# Main_Schematic.net
KiCad netlist of a schematic drawn in Altium Designer
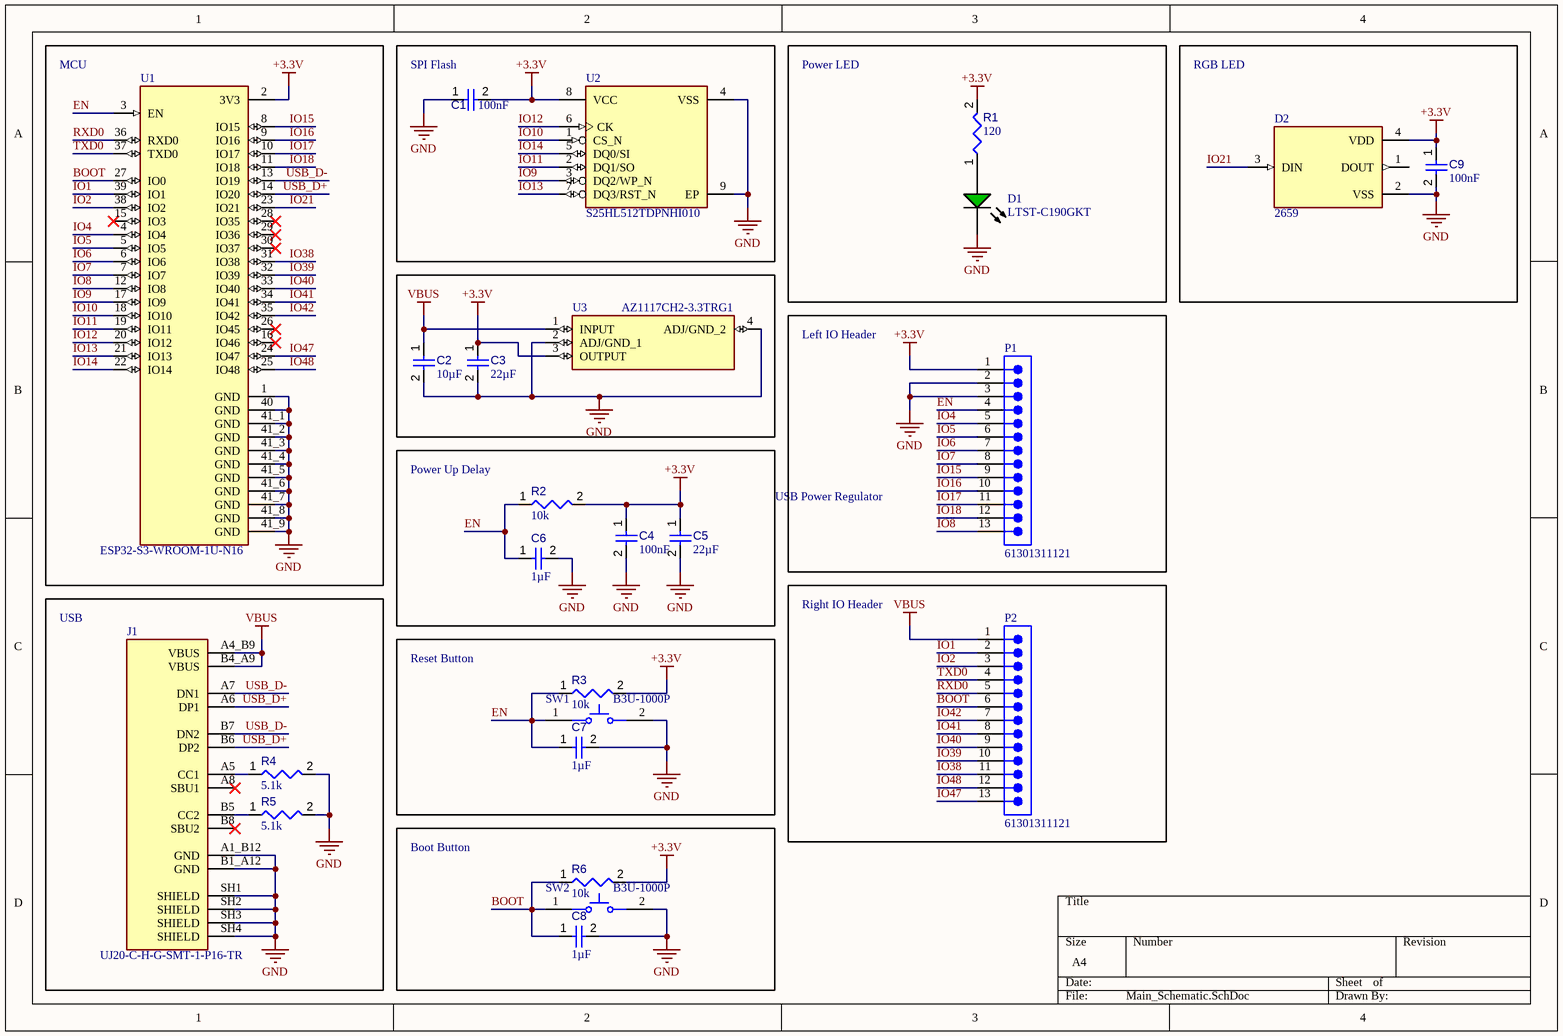
[diagram p0: Main_Schematic.SchDoc]

(export (version "E")
  (design (tool "Eeschema 10.0.6"))
  (components
    (comp (ref "C1")
      (value "100nF")
      (footprint "CAPC1608X90X40NL10T20")
      (description "Chip Capacitor, 100 nF, +/- 10%, 50 V, 0603 (1608 Metric)")
      (fields (field (name "TOLERANCE") "10%") (field (name "Comment") "Capacitor 100 nF +/-10% 50 V 0603"))
      (libsource (lib "Rory Cook") (part "CAP-NP-2"))
    )
    (comp (ref "C2")
      (value "10µF")
      (footprint "CAPC0603(1608)100_L")
      (description "Chip Capacitor, 10µF +/-20%, 10V, 0603, Thickness 1 mm")
      (fields (field (name "TOLERANCE") "10%") (field (name "Comment") "Capacitor 10µF +/-20% 10V 0603"))
      (libsource (lib "Rory Cook") (part "CAP-NP-2"))
    )
    (comp (ref "C3")
      (value "22µF")
      (footprint "CAPC0603(1608)100_L")
      (description "Chip Capacitor, 10µF +/-20%, 10V, 0603, Thickness 1 mm")
      (fields (field (name "TOLERANCE") "10%") (field (name "Comment") "Capacitor 10µF +/-20% 10V 0603"))
      (libsource (lib "Rory Cook") (part "CAP-NP-2"))
    )
    (comp (ref "C4")
      (value "100nF")
      (footprint "CAPC1608X90X40NL10T20")
      (description "Chip Capacitor, 100 nF, +/- 10%, 50 V, 0603 (1608 Metric)")
      (fields (field (name "TOLERANCE") "10%") (field (name "Comment") "Capacitor 100 nF +/-10% 50 V 0603"))
      (libsource (lib "Rory Cook") (part "CAP-NP-2"))
    )
    (comp (ref "C5")
      (value "22µF")
      (footprint "CAPC0603(1608)100_L")
      (description "Chip Capacitor, 10µF +/-20%, 10V, 0603, Thickness 1 mm")
      (fields (field (name "TOLERANCE") "10%") (field (name "Comment") "Capacitor 10µF +/-20% 10V 0603"))
      (libsource (lib "Rory Cook") (part "CAP-NP-2"))
    )
    (comp (ref "C6")
      (value "1µF")
      (footprint "CAPC1608X94X35NL15T15")
      (description "Chip Capacitor, 1 uF, +/- 10%, 16 V, 0603 (1608 Metric)")
      (fields (field (name "TOLERANCE") "10%") (field (name "Comment") "Capacitor 1 uF +/- 10% 16 V 0603"))
      (libsource (lib "Rory Cook") (part "CAP-NP-2"))
    )
    (comp (ref "C7")
      (value "1µF")
      (footprint "CAPC1608X94X35NL15T15")
      (description "Chip Capacitor, 1 uF, +/- 10%, 16 V, 0603 (1608 Metric)")
      (fields (field (name "TOLERANCE") "10%") (field (name "Comment") "Capacitor 1 uF +/- 10% 16 V 0603"))
      (libsource (lib "Rory Cook") (part "CAP-NP-2"))
    )
    (comp (ref "C8")
      (value "1µF")
      (footprint "CAPC1608X94X35NL15T15")
      (description "Chip Capacitor, 1 uF, +/- 10%, 16 V, 0603 (1608 Metric)")
      (fields (field (name "TOLERANCE") "10%") (field (name "Comment") "Capacitor 1 uF +/- 10% 16 V 0603"))
      (libsource (lib "Rory Cook") (part "CAP-NP-2"))
    )
    (comp (ref "C9")
      (value "100nF")
      (footprint "CAPC1608X90X40NL10T20")
      (description "Chip Capacitor, 100 nF, +/- 10%, 50 V, 0603 (1608 Metric)")
      (fields (field (name "TOLERANCE") "10%") (field (name "Comment") "Capacitor 100 nF +/-10% 50 V 0603"))
      (libsource (lib "Rory Cook") (part "CAP-NP-2"))
    )
    (comp (ref "D1")
      (value "LTST-C190GKT")
      (footprint "LTST-C190GKT_V")
      (description "LED Uni-Color Green, 100 mW, 30 mA, -55 to 85 degC, 2-Pin SMD, RoHS, Tape and Reel")
      (fields (field (name "POWER") "100mW") (field (name "MANUFACTURER") "Lite-On"))
      (libsource (lib "Rory Cook") (part "LED-GREEN-AK-2"))
    )
    (comp (ref "D2")
      (value "2659")
      (footprint "2659")
      (description "20 AWG Hook-Up Wire 26/34 White 300V 40.00' _12.19m_")
      (fields (field (name "MF") "Adafruit Industries") (field (name "DIGI-KEY_PART_NUMBER") "2183-2659-ND"))
      (libsource (lib "2659") (part "2659"))
    )
    (comp (ref "J1")
      (value "UJ20-C-H-G-SMT-1-P16-TR")
      (footprint "SAMESKY_UJ20-C-H-G-SMT-1-P16-TR")
      (fields (field (name "MF") "Same Sky"))
      (libsource (lib "Rory Cook") (part "UJ20-C-H-G-SMT-1-P16-TR"))
    )
    (comp (ref "P1")
      (value "61301311121")
      (footprint "61301311121")
      (description "Header, 2.54 Mm, Pin Header, 13 Pins, Single Row, 3A, Wr-phd Series")
      (libsource (lib "Rory Cook") (part "Header_Male_1R_13P"))
    )
    (comp (ref "P2")
      (value "61301311121")
      (footprint "61301311121")
      (description "Header, 2.54 Mm, Pin Header, 13 Pins, Single Row, 3A, Wr-phd Series")
      (libsource (lib "Rory Cook") (part "Header_Male_1R_13P"))
    )
    (comp (ref "R1")
      (value "120")
      (footprint "RESC0603(1608)_L")
      (description "Chip Resistor, 120 Ohms, +/-5 %, 0.1 W, -55 to 155 degC, 0603")
      (fields (field (name "POWER") "100mW") (field (name "TOLERANCE") "5%"))
      (libsource (lib "Rory Cook") (part "RES-2"))
    )
    (comp (ref "R2")
      (value "10k")
      (footprint "RESC1608X55X25ML10T15")
      (description "Chip Resistor, 10 KOhm, +/- 1%, 01 W, -55 to 155 degC, 0603 (1608 Metric)")
      (fields (field (name "POWER") "100mW") (field (name "TOLERANCE") "1%"))
      (libsource (lib "Rory Cook") (part "RES-2"))
    )
    (comp (ref "R3")
      (value "10k")
      (footprint "RESC1608X55X25ML10T15")
      (description "Chip Resistor, 10 KOhm, +/- 1%, 01 W, -55 to 155 degC, 0603 (1608 Metric)")
      (fields (field (name "POWER") "100mW") (field (name "TOLERANCE") "1%"))
      (libsource (lib "Rory Cook") (part "RES-2"))
    )
    (comp (ref "R4")
      (value "5.1k")
      (footprint "RESC1608X55X25ML10T15")
      (description "Chip Resistor, 4.7 KOhm, +/- 1%, 0.1 W, -55 to 155 degC, 0603 (1608 Metric)")
      (fields (field (name "TOLERANCE") "1%") (field (name "POWER") "100mW"))
      (libsource (lib "Rory Cook") (part "RES-2"))
    )
    (comp (ref "R5")
      (value "5.1k")
      (footprint "RESC1608X55X25ML10T15")
      (description "Chip Resistor, 4.7 KOhm, +/- 1%, 0.1 W, -55 to 155 degC, 0603 (1608 Metric)")
      (fields (field (name "TOLERANCE") "1%") (field (name "POWER") "100mW"))
      (libsource (lib "Rory Cook") (part "RES-2"))
    )
    (comp (ref "R6")
      (value "10k")
      (footprint "RESC1608X55X25ML10T15")
      (description "Chip Resistor, 10 KOhm, +/- 1%, 01 W, -55 to 155 degC, 0603 (1608 Metric)")
      (fields (field (name "POWER") "100mW") (field (name "TOLERANCE") "1%"))
      (libsource (lib "Rory Cook") (part "RES-2"))
    )
    (comp (ref "SW1")
      (value "B3U-1000P")
      (footprint "OMRON-B3U-1000_V")
      (description "Tactile Switch, SPST-NO, 0.05 A, 12 V, -25 to 70 degC, 2-Pin SMD, RoHS, Tape and Reel")
      (fields (field (name "MANUFACTURER") "Omron Electronic Components"))
      (libsource (lib "Rory Cook") (part "SW-SPST-NO-2"))
    )
    (comp (ref "SW2")
      (value "B3U-1000P")
      (footprint "OMRON-B3U-1000_V")
      (description "Tactile Switch, SPST-NO, 0.05 A, 12 V, -25 to 70 degC, 2-Pin SMD, RoHS, Tape and Reel")
      (fields (field (name "MANUFACTURER") "Omron Electronic Components"))
      (libsource (lib "Rory Cook") (part "SW-SPST-NO-2"))
    )
    (comp (ref "U1")
      (value "ESP32-S3-WROOM-1U-N16")
      (footprint "XCVR_ESP32-S3-WROOM-1U-N16")
      (fields (field (name "MF") "Espressif Systems"))
      (libsource (lib "Rory Cook") (part "ESP32-S3-WROOM-1U-N16"))
    )
    (comp (ref "U2")
      (value "S25HL512TDPNHI010")
      (footprint "SON127P800X600X80-9N-V1")
      (description "512 Mb, SEMPER Flash Quad SPI")
      (fields (field (name "MANUFACTURER") "Infineon Technologies"))
      (libsource (lib "Rory Cook") (part "S25HL512TDPNHI010"))
    )
    (comp (ref "U3")
      (value "AZ1117CH2-3.3TRG1")
      (footprint "SOT230P700X180-4N")
      (description "Linear Voltage Regulator IC Positive Fixed 1 Output 1A SOT-223-3")
      (fields (field (name "MF") "Diodes Inc."))
      (libsource (lib "AZ1117CH2-3.3TRG1") (part "AZ1117CH2-3.3TRG1"))
    )
  )
  (nets
    (net (code "1") (name "+3.3V") (class "Default")
      (node (ref "C1") (pin "2") (pinfunction "2_2") (pintype "passive"))
      (node (ref "C3") (pin "1") (pinfunction "1_1") (pintype "passive"))
      (node (ref "C4") (pin "1") (pinfunction "1_1") (pintype "passive"))
      (node (ref "C5") (pin "1") (pinfunction "1_1") (pintype "passive"))
      (node (ref "C9") (pin "1") (pinfunction "1_1") (pintype "passive"))
      (node (ref "D2") (pin "4") (pinfunction "VDD_4") (pintype "power_in"))
      (node (ref "P1") (pin "1") (pinfunction "1_1") (pintype "passive"))
      (node (ref "R1") (pin "2") (pinfunction "2_2") (pintype "passive"))
      (node (ref "R2") (pin "2") (pinfunction "2_2") (pintype "passive"))
      (node (ref "R3") (pin "2") (pinfunction "2_2") (pintype "passive"))
      (node (ref "R6") (pin "2") (pinfunction "2_2") (pintype "passive"))
      (node (ref "U1") (pin "2") (pinfunction "3V3_2") (pintype "power_in"))
      (node (ref "U2") (pin "8") (pinfunction "VCC_8") (pintype "power_in"))
      (node (ref "U3") (pin "3") (pinfunction "OUTPUT_3") (pintype "bidirectional"))
    )
    (net (code "2") (name "/BOOT") (class "Default")
      (node (ref "C8") (pin "1") (pinfunction "1_1") (pintype "passive"))
      (node (ref "P2") (pin "6") (pinfunction "6_6") (pintype "passive"))
      (node (ref "R6") (pin "1") (pinfunction "1_1") (pintype "passive"))
      (node (ref "SW2") (pin "1") (pinfunction "1_1") (pintype "passive"))
      (node (ref "U1") (pin "27") (pinfunction "IO0_27") (pintype "bidirectional"))
    )
    (net (code "3") (name "/EN") (class "Default")
      (node (ref "C6") (pin "1") (pinfunction "1_1") (pintype "passive"))
      (node (ref "C7") (pin "1") (pinfunction "1_1") (pintype "passive"))
      (node (ref "P1") (pin "4") (pinfunction "4_4") (pintype "passive"))
      (node (ref "R2") (pin "1") (pinfunction "1_1") (pintype "passive"))
      (node (ref "R3") (pin "1") (pinfunction "1_1") (pintype "passive"))
      (node (ref "SW1") (pin "1") (pinfunction "1_1") (pintype "passive"))
      (node (ref "U1") (pin "3") (pinfunction "EN_3") (pintype "input"))
    )
    (net (code "4") (name "/IO1") (class "Default")
      (node (ref "P2") (pin "2") (pinfunction "2_2") (pintype "passive"))
      (node (ref "U1") (pin "39") (pinfunction "IO1_39") (pintype "bidirectional"))
    )
    (net (code "5") (name "/IO2") (class "Default")
      (node (ref "P2") (pin "3") (pinfunction "3_3") (pintype "passive"))
      (node (ref "U1") (pin "38") (pinfunction "IO2_38") (pintype "bidirectional"))
    )
    (net (code "6") (name "/IO4") (class "Default")
      (node (ref "P1") (pin "5") (pinfunction "5_5") (pintype "passive"))
      (node (ref "U1") (pin "4") (pinfunction "IO4_4") (pintype "bidirectional"))
    )
    (net (code "7") (name "/IO5") (class "Default")
      (node (ref "P1") (pin "6") (pinfunction "6_6") (pintype "passive"))
      (node (ref "U1") (pin "5") (pinfunction "IO5_5") (pintype "bidirectional"))
    )
    (net (code "8") (name "/IO6") (class "Default")
      (node (ref "P1") (pin "7") (pinfunction "7_7") (pintype "passive"))
      (node (ref "U1") (pin "6") (pinfunction "IO6_6") (pintype "bidirectional"))
    )
    (net (code "9") (name "/IO7") (class "Default")
      (node (ref "P1") (pin "8") (pinfunction "8_8") (pintype "passive"))
      (node (ref "U1") (pin "7") (pinfunction "IO7_7") (pintype "bidirectional"))
    )
    (net (code "10") (name "/IO8") (class "Default")
      (node (ref "P1") (pin "13") (pinfunction "13_13") (pintype "passive"))
      (node (ref "U1") (pin "12") (pinfunction "IO8_12") (pintype "bidirectional"))
    )
    (net (code "11") (name "/IO9") (class "Default")
      (node (ref "U1") (pin "17") (pinfunction "IO9_17") (pintype "bidirectional"))
      (node (ref "U2") (pin "3") (pinfunction "DQ2/WP_N_3") (pintype "bidirectional"))
    )
    (net (code "12") (name "/IO10") (class "Default")
      (node (ref "U1") (pin "18") (pinfunction "IO10_18") (pintype "bidirectional"))
      (node (ref "U2") (pin "1") (pinfunction "CS_N_1") (pintype "input"))
    )
    (net (code "13") (name "/IO11") (class "Default")
      (node (ref "U1") (pin "19") (pinfunction "IO11_19") (pintype "bidirectional"))
      (node (ref "U2") (pin "2") (pinfunction "DQ1/SO_2") (pintype "bidirectional"))
    )
    (net (code "14") (name "/IO12") (class "Default")
      (node (ref "U1") (pin "20") (pinfunction "IO12_20") (pintype "bidirectional"))
      (node (ref "U2") (pin "6") (pinfunction "CK_6") (pintype "input"))
    )
    (net (code "15") (name "/IO13") (class "Default")
      (node (ref "U1") (pin "21") (pinfunction "IO13_21") (pintype "bidirectional"))
      (node (ref "U2") (pin "7") (pinfunction "DQ3/RST_N_7") (pintype "bidirectional"))
    )
    (net (code "16") (name "/IO14") (class "Default")
      (node (ref "U1") (pin "22") (pinfunction "IO14_22") (pintype "bidirectional"))
      (node (ref "U2") (pin "5") (pinfunction "DQ0/SI_5") (pintype "bidirectional"))
    )
    (net (code "17") (name "/IO15") (class "Default")
      (node (ref "P1") (pin "9") (pinfunction "9_9") (pintype "passive"))
      (node (ref "U1") (pin "8") (pinfunction "IO15_8") (pintype "bidirectional"))
    )
    (net (code "18") (name "/IO16") (class "Default")
      (node (ref "P1") (pin "10") (pinfunction "10_10") (pintype "passive"))
      (node (ref "U1") (pin "9") (pinfunction "IO16_9") (pintype "bidirectional"))
    )
    (net (code "19") (name "/IO17") (class "Default")
      (node (ref "P1") (pin "11") (pinfunction "11_11") (pintype "passive"))
      (node (ref "U1") (pin "10") (pinfunction "IO17_10") (pintype "bidirectional"))
    )
    (net (code "20") (name "/IO18") (class "Default")
      (node (ref "P1") (pin "12") (pinfunction "12_12") (pintype "passive"))
      (node (ref "U1") (pin "11") (pinfunction "IO18_11") (pintype "bidirectional"))
    )
    (net (code "21") (name "/IO21") (class "Default")
      (node (ref "D2") (pin "3") (pinfunction "DIN_3") (pintype "input"))
      (node (ref "U1") (pin "23") (pinfunction "IO21_23") (pintype "bidirectional"))
    )
    (net (code "22") (name "/IO38") (class "Default")
      (node (ref "P2") (pin "11") (pinfunction "11_11") (pintype "passive"))
      (node (ref "U1") (pin "31") (pinfunction "IO38_31") (pintype "bidirectional"))
    )
    (net (code "23") (name "/IO39") (class "Default")
      (node (ref "P2") (pin "10") (pinfunction "10_10") (pintype "passive"))
      (node (ref "U1") (pin "32") (pinfunction "IO39_32") (pintype "bidirectional"))
    )
    (net (code "24") (name "/IO40") (class "Default")
      (node (ref "P2") (pin "9") (pinfunction "9_9") (pintype "passive"))
      (node (ref "U1") (pin "33") (pinfunction "IO40_33") (pintype "bidirectional"))
    )
    (net (code "25") (name "/IO41") (class "Default")
      (node (ref "P2") (pin "8") (pinfunction "8_8") (pintype "passive"))
      (node (ref "U1") (pin "34") (pinfunction "IO41_34") (pintype "bidirectional"))
    )
    (net (code "26") (name "/IO42") (class "Default")
      (node (ref "P2") (pin "7") (pinfunction "7_7") (pintype "passive"))
      (node (ref "U1") (pin "35") (pinfunction "IO42_35") (pintype "bidirectional"))
    )
    (net (code "27") (name "/IO47") (class "Default")
      (node (ref "P2") (pin "13") (pinfunction "13_13") (pintype "passive"))
      (node (ref "U1") (pin "24") (pinfunction "IO47_24") (pintype "bidirectional"))
    )
    (net (code "28") (name "/IO48") (class "Default")
      (node (ref "P2") (pin "12") (pinfunction "12_12") (pintype "passive"))
      (node (ref "U1") (pin "25") (pinfunction "IO48_25") (pintype "bidirectional"))
    )
    (net (code "29") (name "/RXD0") (class "Default")
      (node (ref "P2") (pin "5") (pinfunction "5_5") (pintype "passive"))
      (node (ref "U1") (pin "36") (pinfunction "RXD0_36") (pintype "bidirectional"))
    )
    (net (code "30") (name "/TXD0") (class "Default")
      (node (ref "P2") (pin "4") (pinfunction "4_4") (pintype "passive"))
      (node (ref "U1") (pin "37") (pinfunction "TXD0_37") (pintype "bidirectional"))
    )
    (net (code "31") (name "/USB_D+") (class "Default")
      (node (ref "J1") (pin "A6") (pinfunction "DP1_A6") (pintype "passive"))
      (node (ref "J1") (pin "B6") (pinfunction "DP2_B6") (pintype "passive"))
      (node (ref "U1") (pin "14") (pinfunction "IO20_14") (pintype "bidirectional"))
    )
    (net (code "32") (name "/USB_D-") (class "Default")
      (node (ref "J1") (pin "A7") (pinfunction "DN1_A7") (pintype "passive"))
      (node (ref "J1") (pin "B7") (pinfunction "DN2_B7") (pintype "passive"))
      (node (ref "U1") (pin "13") (pinfunction "IO19_13") (pintype "bidirectional"))
    )
    (net (code "33") (name "GND") (class "Default")
      (node (ref "C1") (pin "1") (pinfunction "1_1") (pintype "passive"))
      (node (ref "C2") (pin "2") (pinfunction "2_2") (pintype "passive"))
      (node (ref "C3") (pin "2") (pinfunction "2_2") (pintype "passive"))
      (node (ref "C4") (pin "2") (pinfunction "2_2") (pintype "passive"))
      (node (ref "C5") (pin "2") (pinfunction "2_2") (pintype "passive"))
      (node (ref "C6") (pin "2") (pinfunction "2_2") (pintype "passive"))
      (node (ref "C7") (pin "2") (pinfunction "2_2") (pintype "passive"))
      (node (ref "C8") (pin "2") (pinfunction "2_2") (pintype "passive"))
      (node (ref "C9") (pin "2") (pinfunction "2_2") (pintype "passive"))
      (node (ref "D1") (pin "2") (pinfunction "K_2") (pintype "passive"))
      (node (ref "D2") (pin "2") (pinfunction "VSS_2") (pintype "power_in"))
      (node (ref "J1") (pin "A1_B12") (pinfunction "GND_A1_B12") (pintype "passive"))
      (node (ref "J1") (pin "B1_A12") (pinfunction "GND_B1_A12") (pintype "passive"))
      (node (ref "J1") (pin "SH1") (pinfunction "SHIELD_SH1") (pintype "passive"))
      (node (ref "J1") (pin "SH2") (pinfunction "SHIELD_SH2") (pintype "passive"))
      (node (ref "J1") (pin "SH3") (pinfunction "SHIELD_SH3") (pintype "passive"))
      (node (ref "J1") (pin "SH4") (pinfunction "SHIELD_SH4") (pintype "passive"))
      (node (ref "P1") (pin "2") (pinfunction "2_2") (pintype "passive"))
      (node (ref "P1") (pin "3") (pinfunction "3_3") (pintype "passive"))
      (node (ref "R4") (pin "2") (pinfunction "2_2") (pintype "passive"))
      (node (ref "R5") (pin "2") (pinfunction "2_2") (pintype "passive"))
      (node (ref "SW1") (pin "2") (pinfunction "2_2") (pintype "passive"))
      (node (ref "SW2") (pin "2") (pinfunction "2_2") (pintype "passive"))
      (node (ref "U1") (pin "1") (pinfunction "GND_1") (pintype "power_in"))
      (node (ref "U1") (pin "40") (pinfunction "GND_40") (pintype "power_in"))
      (node (ref "U1") (pin "41_1") (pinfunction "GND_41_1") (pintype "power_in"))
      (node (ref "U1") (pin "41_2") (pinfunction "GND_41_2") (pintype "power_in"))
      (node (ref "U1") (pin "41_3") (pinfunction "GND_41_3") (pintype "power_in"))
      (node (ref "U1") (pin "41_4") (pinfunction "GND_41_4") (pintype "power_in"))
      (node (ref "U1") (pin "41_5") (pinfunction "GND_41_5") (pintype "power_in"))
      (node (ref "U1") (pin "41_6") (pinfunction "GND_41_6") (pintype "power_in"))
      (node (ref "U1") (pin "41_7") (pinfunction "GND_41_7") (pintype "power_in"))
      (node (ref "U1") (pin "41_8") (pinfunction "GND_41_8") (pintype "power_in"))
      (node (ref "U1") (pin "41_9") (pinfunction "GND_41_9") (pintype "power_in"))
      (node (ref "U2") (pin "4") (pinfunction "VSS_4") (pintype "power_in"))
      (node (ref "U2") (pin "9") (pinfunction "EP_9") (pintype "power_in"))
      (node (ref "U3") (pin "2") (pinfunction "ADJ/GND_1_2") (pintype "bidirectional"))
      (node (ref "U3") (pin "4") (pinfunction "ADJ/GND_2_4") (pintype "bidirectional"))
    )
    (net (code "34") (name "Net-(D1-A)") (class "Default")
      (node (ref "D1") (pin "1") (pinfunction "A_1") (pintype "passive"))
      (node (ref "R1") (pin "1") (pinfunction "1_1") (pintype "passive"))
    )
    (net (code "35") (name "Net-(J1-CC1)") (class "Default")
      (node (ref "J1") (pin "A5") (pinfunction "CC1_A5") (pintype "passive"))
      (node (ref "R4") (pin "1") (pinfunction "1_1") (pintype "passive"))
    )
    (net (code "36") (name "Net-(J1-CC2)") (class "Default")
      (node (ref "J1") (pin "B5") (pinfunction "CC2_B5") (pintype "passive"))
      (node (ref "R5") (pin "1") (pinfunction "1_1") (pintype "passive"))
    )
    (net (code "37") (name "VBUS") (class "Default")
      (node (ref "C2") (pin "1") (pinfunction "1_1") (pintype "passive"))
      (node (ref "J1") (pin "A4_B9") (pinfunction "VBUS_A4_B9") (pintype "passive"))
      (node (ref "J1") (pin "B4_A9") (pinfunction "VBUS_B4_A9") (pintype "passive"))
      (node (ref "P2") (pin "1") (pinfunction "1_1") (pintype "passive"))
      (node (ref "U3") (pin "1") (pinfunction "INPUT_1") (pintype "bidirectional"))
    )
    (net (code "38") (name "unconnected-(D2-DOUT-Pad1)") (class "Default")
      (node (ref "D2") (pin "1") (pinfunction "DOUT_1") (pintype "output"))
    )
    (net (code "39") (name "unconnected-(J1-SBU1-PadA8)") (class "Default")
      (node (ref "J1") (pin "A8") (pinfunction "SBU1_A8") (pintype "passive+no_connect"))
    )
    (net (code "40") (name "unconnected-(J1-SBU2-PadB8)") (class "Default")
      (node (ref "J1") (pin "B8") (pinfunction "SBU2_B8") (pintype "passive+no_connect"))
    )
    (net (code "41") (name "unconnected-(U1-IO3-Pad15)") (class "Default")
      (node (ref "U1") (pin "15") (pinfunction "IO3_15") (pintype "bidirectional+no_connect"))
    )
    (net (code "42") (name "unconnected-(U1-IO35-Pad28)") (class "Default")
      (node (ref "U1") (pin "28") (pinfunction "IO35_28") (pintype "bidirectional+no_connect"))
    )
    (net (code "43") (name "unconnected-(U1-IO36-Pad29)") (class "Default")
      (node (ref "U1") (pin "29") (pinfunction "IO36_29") (pintype "bidirectional+no_connect"))
    )
    (net (code "44") (name "unconnected-(U1-IO37-Pad30)") (class "Default")
      (node (ref "U1") (pin "30") (pinfunction "IO37_30") (pintype "bidirectional+no_connect"))
    )
    (net (code "45") (name "unconnected-(U1-IO45-Pad26)") (class "Default")
      (node (ref "U1") (pin "26") (pinfunction "IO45_26") (pintype "bidirectional+no_connect"))
    )
    (net (code "46") (name "unconnected-(U1-IO46-Pad16)") (class "Default")
      (node (ref "U1") (pin "16") (pinfunction "IO46_16") (pintype "bidirectional+no_connect"))
    )
  )
)
